# Schematic.net
KiCad netlist of a schematic drawn in EAGLE
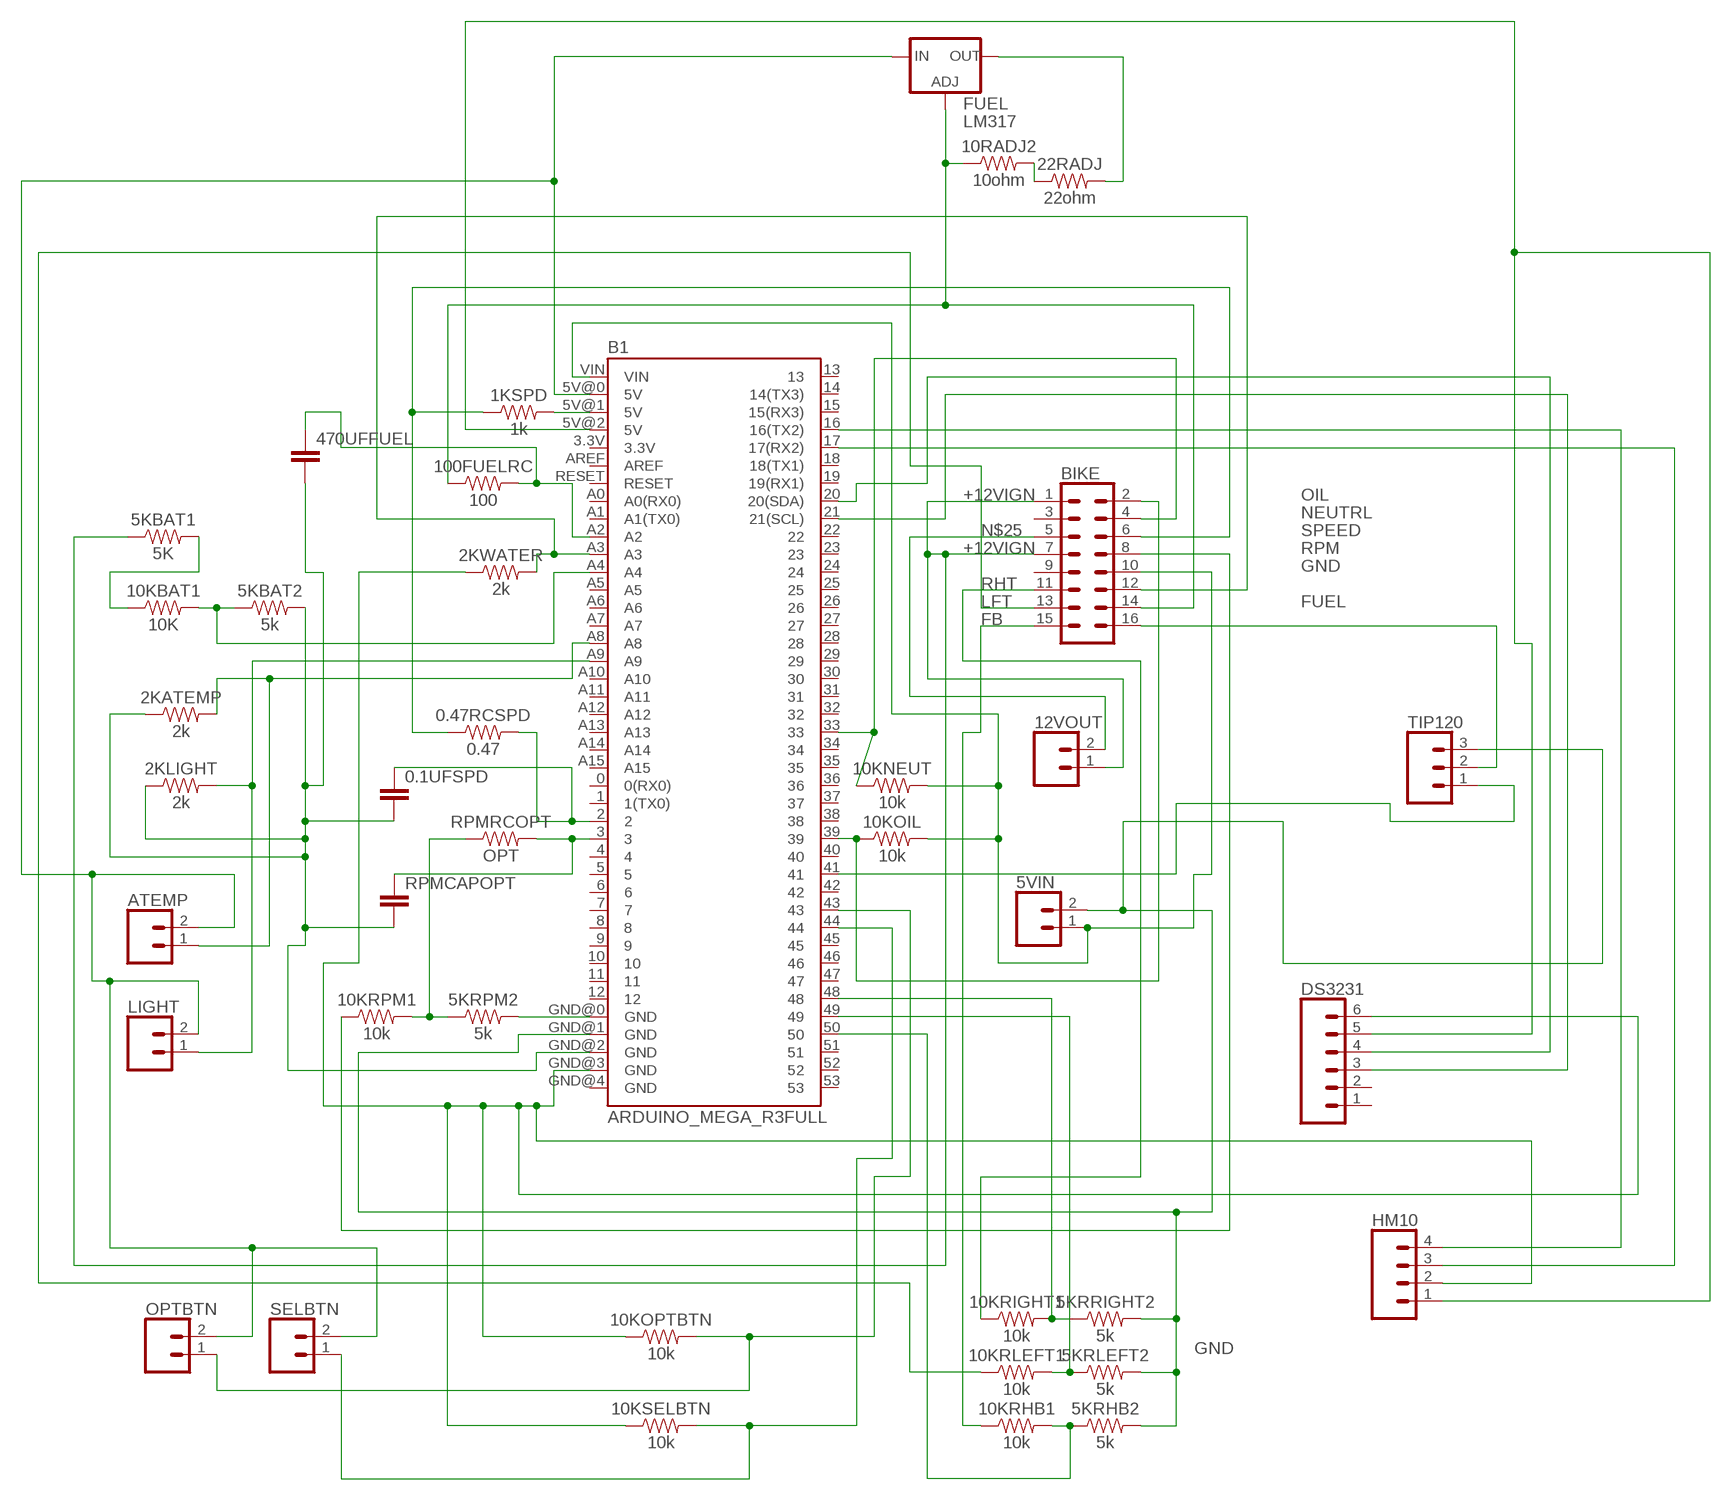
[diagram p0: schematic, sheet 1]

(export (version "E")
  (design (tool "Eeschema 10.0.6"))
  (components
    (comp (ref "0.1UFSPD")
      (value "C2,5-3")
      (footprint "eagle-import:C2.5-3")
      (libsource (lib "eagle-import") (part "C2,5-3"))
    )
    (comp (ref "0.47RCSPD")
      (value "0.47")
      (footprint "eagle-import:AXIAL-0.3")
      (libsource (lib "eagle-import") (part "1KOHM-HORIZ-1/4W-5%"))
    )
    (comp (ref "1KSPD")
      (value "1k")
      (footprint "eagle-import:AXIAL-0.3")
      (libsource (lib "eagle-import") (part "1KOHM-HORIZ-1/4W-5%"))
    )
    (comp (ref "2KATEMP")
      (value "2k")
      (footprint "eagle-import:AXIAL-0.3")
      (libsource (lib "eagle-import") (part "1KOHM-HORIZ-1/4W-5%"))
    )
    (comp (ref "2KLIGHT")
      (value "2k")
      (footprint "eagle-import:AXIAL-0.3")
      (libsource (lib "eagle-import") (part "1KOHM-HORIZ-1/4W-5%"))
    )
    (comp (ref "2KWATER")
      (value "2k")
      (footprint "eagle-import:AXIAL-0.3")
      (libsource (lib "eagle-import") (part "1KOHM-HORIZ-1/4W-5%"))
    )
    (comp (ref "5KBAT1")
      (value "5K")
      (footprint "eagle-import:AXIAL-0.3")
      (libsource (lib "eagle-import") (part "1KOHM-HORIZ-1/4W-5%"))
    )
    (comp (ref "5KBAT2")
      (value "5k")
      (footprint "eagle-import:AXIAL-0.3")
      (libsource (lib "eagle-import") (part "1KOHM-HORIZ-1/4W-5%"))
    )
    (comp (ref "5KRHB2")
      (value "5k")
      (footprint "eagle-import:AXIAL-0.3")
      (libsource (lib "eagle-import") (part "1KOHM-HORIZ-1/4W-5%"))
    )
    (comp (ref "5KRLEFT2")
      (value "5k")
      (footprint "eagle-import:AXIAL-0.3")
      (libsource (lib "eagle-import") (part "1KOHM-HORIZ-1/4W-5%"))
    )
    (comp (ref "5KRPM2")
      (value "5k")
      (footprint "eagle-import:AXIAL-0.3")
      (libsource (lib "eagle-import") (part "1KOHM-HORIZ-1/4W-5%"))
    )
    (comp (ref "5KRRIGHT2")
      (value "5k")
      (footprint "eagle-import:AXIAL-0.3")
      (libsource (lib "eagle-import") (part "1KOHM-HORIZ-1/4W-5%"))
    )
    (comp (ref "5VIN")
      (value "CONN_02PTH4")
      (footprint "eagle-import:1X02_XTRA_BIG")
      (libsource (lib "eagle-import") (part "CONN_02PTH4"))
    )
    (comp (ref "10KBAT1")
      (value "10K")
      (footprint "eagle-import:AXIAL-0.3")
      (libsource (lib "eagle-import") (part "1KOHM-HORIZ-1/4W-5%"))
    )
    (comp (ref "10KNEUT")
      (value "10k")
      (footprint "eagle-import:AXIAL-0.3")
      (libsource (lib "eagle-import") (part "1KOHM-HORIZ-1/4W-5%"))
    )
    (comp (ref "10KOIL")
      (value "10k")
      (footprint "eagle-import:AXIAL-0.3")
      (libsource (lib "eagle-import") (part "1KOHM-HORIZ-1/4W-5%"))
    )
    (comp (ref "10KOPTBTN")
      (value "10k")
      (footprint "eagle-import:AXIAL-0.3")
      (libsource (lib "eagle-import") (part "1KOHM-HORIZ-1/4W-5%"))
    )
    (comp (ref "10KRHB1")
      (value "10k")
      (footprint "eagle-import:AXIAL-0.3")
      (libsource (lib "eagle-import") (part "1KOHM-HORIZ-1/4W-5%"))
    )
    (comp (ref "10KRIGHT1")
      (value "10k")
      (footprint "eagle-import:AXIAL-0.3")
      (libsource (lib "eagle-import") (part "1KOHM-HORIZ-1/4W-5%"))
    )
    (comp (ref "10KRLEFT1")
      (value "10k")
      (footprint "eagle-import:AXIAL-0.3")
      (libsource (lib "eagle-import") (part "1KOHM-HORIZ-1/4W-5%"))
    )
    (comp (ref "10KRPM1")
      (value "10k")
      (footprint "eagle-import:AXIAL-0.3")
      (libsource (lib "eagle-import") (part "1KOHM-HORIZ-1/4W-5%"))
    )
    (comp (ref "10KSELBTN")
      (value "10k")
      (footprint "eagle-import:AXIAL-0.3")
      (libsource (lib "eagle-import") (part "1KOHM-HORIZ-1/4W-5%"))
    )
    (comp (ref "10RADJ2")
      (value "10ohm")
      (footprint "eagle-import:AXIAL-0.3")
      (libsource (lib "eagle-import") (part "1KOHM-HORIZ-1/4W-5%"))
    )
    (comp (ref "12VOUT")
      (value "CONN_02PTH4")
      (footprint "eagle-import:1X02_XTRA_BIG")
      (libsource (lib "eagle-import") (part "CONN_02PTH4"))
    )
    (comp (ref "22RADJ")
      (value "22ohm")
      (footprint "eagle-import:AXIAL-0.3")
      (libsource (lib "eagle-import") (part "1KOHM-HORIZ-1/4W-5%"))
    )
    (comp (ref "100FUELRC")
      (value "100")
      (footprint "eagle-import:AXIAL-0.3")
      (libsource (lib "eagle-import") (part "1KOHM-HORIZ-1/4W-5%"))
    )
    (comp (ref "470UFFUEL")
      (value "C2,5-3")
      (footprint "eagle-import:C2.5-3")
      (libsource (lib "eagle-import") (part "C2,5-3"))
    )
    (comp (ref "ATEMP")
      (value "CONN_02")
      (footprint "eagle-import:1X02")
      (libsource (lib "eagle-import") (part "CONN_02"))
    )
    (comp (ref "B1")
      (value "ARDUINO_MEGA_R3FULL")
      (footprint "eagle-import:ARDUINO_MEGA")
      (libsource (lib "eagle-import") (part "ARDUINO_MEGA_R3FULL"))
    )
    (comp (ref "BIKE")
      (value "CONN_08X2")
      (footprint "eagle-import:2X8")
      (libsource (lib "eagle-import") (part "CONN_08X2"))
    )
    (comp (ref "DS3231")
      (value "CONN_06SILK_FEMALE_PTH")
      (footprint "eagle-import:1X06")
      (libsource (lib "eagle-import") (part "CONN_06SILK_FEMALE_PTH"))
    )
    (comp (ref "FUEL")
      (value "LM317")
      (footprint "eagle-import:TO220-ADJ")
      (libsource (lib "eagle-import") (part "V_REG_317SINK"))
    )
    (comp (ref "HM10")
      (value "CONN_04")
      (footprint "eagle-import:1X04")
      (libsource (lib "eagle-import") (part "CONN_04"))
    )
    (comp (ref "LIGHT")
      (value "CONN_02")
      (footprint "eagle-import:1X02")
      (libsource (lib "eagle-import") (part "CONN_02"))
    )
    (comp (ref "OPTBTN")
      (value "CONN_02")
      (footprint "eagle-import:1X02")
      (libsource (lib "eagle-import") (part "CONN_02"))
    )
    (comp (ref "RPMCAPOPT")
      (value "C2,5-3")
      (footprint "eagle-import:C2.5-3")
      (libsource (lib "eagle-import") (part "C2,5-3"))
    )
    (comp (ref "RPMRCOPT")
      (value "OPT")
      (footprint "eagle-import:AXIAL-0.3")
      (libsource (lib "eagle-import") (part "1KOHM-HORIZ-1/4W-5%"))
    )
    (comp (ref "SELBTN")
      (value "CONN_02")
      (footprint "eagle-import:1X02")
      (libsource (lib "eagle-import") (part "CONN_02"))
    )
    (comp (ref "TIP120")
      (value "CONN_03")
      (footprint "eagle-import:1X03")
      (libsource (lib "eagle-import") (part "CONN_03"))
    )
  )
  (nets
    (net (code "1") (name "/+12VIGN") (class "Default")
      (node (ref "12VOUT") (pin "1") (pinfunction "1_1") (pintype "passive"))
      (node (ref "5KBAT1") (pin "P$1") (pinfunction "1_P$1") (pintype "passive"))
      (node (ref "BIKE") (pin "1") (pinfunction "1_1") (pintype "passive"))
      (node (ref "BIKE") (pin "7") (pinfunction "7_7") (pintype "passive"))
    )
    (net (code "2") (name "/FB") (class "Default")
      (node (ref "10KRHB1") (pin "P$1") (pinfunction "1_P$1") (pintype "passive"))
      (node (ref "BIKE") (pin "15") (pinfunction "15_15") (pintype "passive"))
    )
    (net (code "3") (name "/FUEL") (class "Default")
      (node (ref "100FUELRC") (pin "P$1") (pinfunction "1_P$1") (pintype "passive"))
      (node (ref "10RADJ2") (pin "P$1") (pinfunction "1_P$1") (pintype "passive"))
      (node (ref "BIKE") (pin "14") (pinfunction "14_14") (pintype "passive"))
      (node (ref "FUEL") (pin "ADJ") (pinfunction "ADJ_ADJ") (pintype "input"))
    )
    (net (code "4") (name "/GND") (class "Default")
      (node (ref "5KRHB2") (pin "P$2") (pinfunction "2_P$2") (pintype "passive"))
      (node (ref "5KRLEFT2") (pin "P$2") (pinfunction "2_P$2") (pintype "passive"))
      (node (ref "5KRRIGHT2") (pin "P$2") (pinfunction "2_P$2") (pintype "passive"))
      (node (ref "5VIN") (pin "2") (pinfunction "2_2") (pintype "passive"))
      (node (ref "B1") (pin "GND@1") (pinfunction "GND_GND@1") (pintype "bidirectional"))
      (node (ref "TIP120") (pin "3") (pinfunction "3_3") (pintype "passive"))
    )
    (net (code "5") (name "/LFT") (class "Default")
      (node (ref "10KRLEFT1") (pin "P$1") (pinfunction "1_P$1") (pintype "passive"))
      (node (ref "BIKE") (pin "13") (pinfunction "13_13") (pintype "passive"))
    )
    (net (code "6") (name "/N$25") (class "Default")
      (node (ref "12VOUT") (pin "2") (pinfunction "2_2") (pintype "passive"))
      (node (ref "BIKE") (pin "5") (pinfunction "5_5") (pintype "passive"))
    )
    (net (code "7") (name "/NEUTRL") (class "Default")
      (node (ref "10KNEUT") (pin "P$1") (pinfunction "1_P$1") (pintype "passive"))
      (node (ref "B1") (pin "33") (pinfunction "33_33") (pintype "bidirectional"))
      (node (ref "BIKE") (pin "4") (pinfunction "4_4") (pintype "passive"))
    )
    (net (code "8") (name "/OIL") (class "Default")
      (node (ref "10KOIL") (pin "P$1") (pinfunction "1_P$1") (pintype "passive"))
      (node (ref "B1") (pin "39") (pinfunction "39_39") (pintype "bidirectional"))
      (node (ref "BIKE") (pin "2") (pinfunction "2_2") (pintype "passive"))
    )
    (net (code "9") (name "/RHT") (class "Default")
      (node (ref "10KRIGHT1") (pin "P$1") (pinfunction "1_P$1") (pintype "passive"))
      (node (ref "BIKE") (pin "11") (pinfunction "11_11") (pintype "passive"))
    )
    (net (code "10") (name "/RPM") (class "Default")
      (node (ref "10KRPM1") (pin "P$1") (pinfunction "1_P$1") (pintype "passive"))
      (node (ref "BIKE") (pin "8") (pinfunction "8_8") (pintype "passive"))
    )
    (net (code "11") (name "/SPEED") (class "Default")
      (node (ref "0.47RCSPD") (pin "P$1") (pinfunction "1_P$1") (pintype "passive"))
      (node (ref "1KSPD") (pin "P$1") (pinfunction "1_P$1") (pintype "passive"))
      (node (ref "BIKE") (pin "6") (pinfunction "6_6") (pintype "passive"))
    )
    (net (code "12") (name "Net-(0.47RCSPD-2)") (class "Default")
      (node (ref "0.1UFSPD") (pin "1") (pinfunction "1_1") (pintype "passive"))
      (node (ref "0.47RCSPD") (pin "P$2") (pinfunction "2_P$2") (pintype "passive"))
      (node (ref "B1") (pin "2") (pinfunction "2_2") (pintype "bidirectional"))
    )
    (net (code "13") (name "Net-(1KSPD-2)") (class "Default")
      (node (ref "1KSPD") (pin "P$2") (pinfunction "2_P$2") (pintype "passive"))
      (node (ref "B1") (pin "5V@1") (pinfunction "5V_5V@1") (pintype "bidirectional"))
    )
    (net (code "14") (name "Net-(2KATEMP-1)") (class "Default")
      (node (ref "0.1UFSPD") (pin "2") (pinfunction "2_2") (pintype "passive"))
      (node (ref "2KATEMP") (pin "P$1") (pinfunction "1_P$1") (pintype "passive"))
      (node (ref "2KLIGHT") (pin "P$1") (pinfunction "1_P$1") (pintype "passive"))
      (node (ref "470UFFUEL") (pin "2") (pinfunction "2_2") (pintype "passive"))
      (node (ref "5KBAT2") (pin "P$2") (pinfunction "2_P$2") (pintype "passive"))
      (node (ref "B1") (pin "GND@2") (pinfunction "GND_GND@2") (pintype "bidirectional"))
      (node (ref "RPMCAPOPT") (pin "2") (pinfunction "2_2") (pintype "passive"))
    )
    (net (code "15") (name "Net-(2KATEMP-2)") (class "Default")
      (node (ref "2KATEMP") (pin "P$2") (pinfunction "2_P$2") (pintype "passive"))
      (node (ref "ATEMP") (pin "1") (pinfunction "1_1") (pintype "passive"))
      (node (ref "B1") (pin "A8") (pinfunction "A8_A8") (pintype "bidirectional"))
    )
    (net (code "16") (name "Net-(2KLIGHT-2)") (class "Default")
      (node (ref "2KLIGHT") (pin "P$2") (pinfunction "2_P$2") (pintype "passive"))
      (node (ref "B1") (pin "A9") (pinfunction "A9_A9") (pintype "bidirectional"))
      (node (ref "LIGHT") (pin "1") (pinfunction "1_1") (pintype "passive"))
    )
    (net (code "17") (name "Net-(2KWATER-2)") (class "Default")
      (node (ref "2KWATER") (pin "P$2") (pinfunction "2_P$2") (pintype "passive"))
      (node (ref "B1") (pin "A3") (pinfunction "A3_A3") (pintype "bidirectional"))
      (node (ref "BIKE") (pin "12") (pinfunction "12_12") (pintype "passive"))
    )
    (net (code "18") (name "Net-(5KRPM2-2)") (class "Default")
      (node (ref "5KRPM2") (pin "P$2") (pinfunction "2_P$2") (pintype "passive"))
      (node (ref "B1") (pin "GND@0") (pinfunction "GND_GND@0") (pintype "bidirectional"))
    )
    (net (code "19") (name "Net-(10KBAT1-1)") (class "Default")
      (node (ref "10KBAT1") (pin "P$1") (pinfunction "1_P$1") (pintype "passive"))
      (node (ref "5KBAT1") (pin "P$2") (pinfunction "2_P$2") (pintype "passive"))
    )
    (net (code "20") (name "Net-(10KBAT1-2)") (class "Default")
      (node (ref "10KBAT1") (pin "P$2") (pinfunction "2_P$2") (pintype "passive"))
      (node (ref "5KBAT2") (pin "P$1") (pinfunction "1_P$1") (pintype "passive"))
      (node (ref "B1") (pin "A4") (pinfunction "A4_A4") (pintype "bidirectional"))
    )
    (net (code "21") (name "Net-(10KNEUT-2)") (class "Default")
      (node (ref "10KNEUT") (pin "P$2") (pinfunction "2_P$2") (pintype "passive"))
      (node (ref "10KOIL") (pin "P$2") (pinfunction "2_P$2") (pintype "passive"))
      (node (ref "5VIN") (pin "1") (pinfunction "1_1") (pintype "passive"))
      (node (ref "B1") (pin "VIN") (pinfunction "VIN_VIN") (pintype "bidirectional"))
      (node (ref "BIKE") (pin "10") (pinfunction "10_10") (pintype "passive"))
    )
    (net (code "22") (name "Net-(10KOPTBTN-1)") (class "Default")
      (node (ref "10KOPTBTN") (pin "P$1") (pinfunction "1_P$1") (pintype "passive"))
      (node (ref "10KSELBTN") (pin "P$1") (pinfunction "1_P$1") (pintype "passive"))
      (node (ref "2KWATER") (pin "P$1") (pinfunction "1_P$1") (pintype "passive"))
      (node (ref "B1") (pin "GND@3") (pinfunction "GND_GND@3") (pintype "bidirectional"))
      (node (ref "DS3231") (pin "6") (pinfunction "6_6") (pintype "passive"))
      (node (ref "HM10") (pin "2") (pinfunction "2_2") (pintype "passive"))
    )
    (net (code "23") (name "Net-(10KOPTBTN-2)") (class "Default")
      (node (ref "10KOPTBTN") (pin "P$2") (pinfunction "2_P$2") (pintype "passive"))
      (node (ref "B1") (pin "43") (pinfunction "43_43") (pintype "bidirectional"))
      (node (ref "OPTBTN") (pin "1") (pinfunction "1_1") (pintype "passive"))
    )
    (net (code "24") (name "Net-(10KRHB1-2)") (class "Default")
      (node (ref "10KRHB1") (pin "P$2") (pinfunction "2_P$2") (pintype "passive"))
      (node (ref "5KRHB2") (pin "P$1") (pinfunction "1_P$1") (pintype "passive"))
      (node (ref "B1") (pin "50") (pinfunction "50_50") (pintype "bidirectional"))
    )
    (net (code "25") (name "Net-(10KRIGHT1-2)") (class "Default")
      (node (ref "10KRIGHT1") (pin "P$2") (pinfunction "2_P$2") (pintype "passive"))
      (node (ref "5KRRIGHT2") (pin "P$1") (pinfunction "1_P$1") (pintype "passive"))
      (node (ref "B1") (pin "48") (pinfunction "48_48") (pintype "bidirectional"))
    )
    (net (code "26") (name "Net-(10KRLEFT1-2)") (class "Default")
      (node (ref "10KRLEFT1") (pin "P$2") (pinfunction "2_P$2") (pintype "passive"))
      (node (ref "5KRLEFT2") (pin "P$1") (pinfunction "1_P$1") (pintype "passive"))
      (node (ref "B1") (pin "49") (pinfunction "49_49") (pintype "bidirectional"))
    )
    (net (code "27") (name "Net-(10KRPM1-2)") (class "Default")
      (node (ref "10KRPM1") (pin "P$2") (pinfunction "2_P$2") (pintype "passive"))
      (node (ref "5KRPM2") (pin "P$1") (pinfunction "1_P$1") (pintype "passive"))
      (node (ref "RPMRCOPT") (pin "P$1") (pinfunction "1_P$1") (pintype "passive"))
    )
    (net (code "28") (name "Net-(10KSELBTN-2)") (class "Default")
      (node (ref "10KSELBTN") (pin "P$2") (pinfunction "2_P$2") (pintype "passive"))
      (node (ref "B1") (pin "44") (pinfunction "44_44") (pintype "bidirectional"))
      (node (ref "SELBTN") (pin "1") (pinfunction "1_1") (pintype "passive"))
    )
    (net (code "29") (name "Net-(10RADJ2-2)") (class "Default")
      (node (ref "10RADJ2") (pin "P$2") (pinfunction "2_P$2") (pintype "passive"))
      (node (ref "22RADJ") (pin "P$1") (pinfunction "1_P$1") (pintype "passive"))
    )
    (net (code "30") (name "Net-(22RADJ-2)") (class "Default")
      (node (ref "22RADJ") (pin "P$2") (pinfunction "2_P$2") (pintype "passive"))
      (node (ref "FUEL") (pin "OUT") (pinfunction "OUT_OUT") (pintype "output"))
    )
    (net (code "31") (name "Net-(100FUELRC-2)") (class "Default")
      (node (ref "100FUELRC") (pin "P$2") (pinfunction "2_P$2") (pintype "passive"))
      (node (ref "470UFFUEL") (pin "1") (pinfunction "1_1") (pintype "passive"))
      (node (ref "B1") (pin "A2") (pinfunction "A2_A2") (pintype "bidirectional"))
    )
    (net (code "32") (name "Net-(ATEMP-Pad2)") (class "Default")
      (node (ref "ATEMP") (pin "2") (pinfunction "2_2") (pintype "passive"))
      (node (ref "B1") (pin "5V@0") (pinfunction "5V_5V@0") (pintype "bidirectional"))
      (node (ref "FUEL") (pin "IN") (pinfunction "IN_IN") (pintype "input"))
      (node (ref "LIGHT") (pin "2") (pinfunction "2_2") (pintype "passive"))
      (node (ref "OPTBTN") (pin "2") (pinfunction "2_2") (pintype "passive"))
      (node (ref "SELBTN") (pin "2") (pinfunction "2_2") (pintype "passive"))
    )
    (net (code "33") (name "Net-(B1-5V-Pad5V@2)") (class "Default")
      (node (ref "B1") (pin "5V@2") (pinfunction "5V_5V@2") (pintype "bidirectional"))
      (node (ref "DS3231") (pin "5") (pinfunction "5_5") (pintype "passive"))
      (node (ref "HM10") (pin "1") (pinfunction "1_1") (pintype "passive"))
    )
    (net (code "34") (name "Net-(B1-16(TX2))") (class "Default")
      (node (ref "B1") (pin "16") (pinfunction "16(TX2)_16") (pintype "bidirectional"))
      (node (ref "HM10") (pin "4") (pinfunction "4_4") (pintype "passive"))
    )
    (net (code "35") (name "Net-(B1-17(RX2))") (class "Default")
      (node (ref "B1") (pin "17") (pinfunction "17(RX2)_17") (pintype "bidirectional"))
      (node (ref "HM10") (pin "3") (pinfunction "3_3") (pintype "passive"))
    )
    (net (code "36") (name "Net-(B1-20(SDA))") (class "Default")
      (node (ref "B1") (pin "20") (pinfunction "20(SDA)_20") (pintype "bidirectional"))
      (node (ref "DS3231") (pin "4") (pinfunction "4_4") (pintype "passive"))
    )
    (net (code "37") (name "Net-(B1-21(SCL))") (class "Default")
      (node (ref "B1") (pin "21") (pinfunction "21(SCL)_21") (pintype "bidirectional"))
      (node (ref "DS3231") (pin "3") (pinfunction "3_3") (pintype "passive"))
    )
    (net (code "38") (name "Net-(B1-Pad41)") (class "Default")
      (node (ref "B1") (pin "41") (pinfunction "41_41") (pintype "bidirectional"))
      (node (ref "TIP120") (pin "1") (pinfunction "1_1") (pintype "passive"))
    )
    (net (code "39") (name "Net-(BIKE-Pad16)") (class "Default")
      (node (ref "BIKE") (pin "16") (pinfunction "16_16") (pintype "passive"))
      (node (ref "TIP120") (pin "2") (pinfunction "2_2") (pintype "passive"))
    )
    (net (code "40") (name "Net-(RPMRCOPT-2)") (class "Default")
      (node (ref "B1") (pin "3") (pinfunction "3_3") (pintype "bidirectional"))
      (node (ref "RPMCAPOPT") (pin "1") (pinfunction "1_1") (pintype "passive"))
      (node (ref "RPMRCOPT") (pin "P$2") (pinfunction "2_P$2") (pintype "passive"))
    )
    (net (code "41") (name "unconnected-(B1-0(RX0)-Pad0)") (class "Default")
      (node (ref "B1") (pin "0") (pinfunction "0(RX0)_0") (pintype "bidirectional"))
    )
    (net (code "42") (name "unconnected-(B1-1(TX0)-Pad1)") (class "Default")
      (node (ref "B1") (pin "1") (pinfunction "1(TX0)_1") (pintype "bidirectional"))
    )
    (net (code "43") (name "unconnected-(B1-14(TX3)-Pad14)") (class "Default")
      (node (ref "B1") (pin "14") (pinfunction "14(TX3)_14") (pintype "bidirectional"))
    )
    (net (code "44") (name "unconnected-(B1-15(RX3)-Pad15)") (class "Default")
      (node (ref "B1") (pin "15") (pinfunction "15(RX3)_15") (pintype "bidirectional"))
    )
    (net (code "45") (name "unconnected-(B1-18(TX1)-Pad18)") (class "Default")
      (node (ref "B1") (pin "18") (pinfunction "18(TX1)_18") (pintype "bidirectional"))
    )
    (net (code "46") (name "unconnected-(B1-19(RX1)-Pad19)") (class "Default")
      (node (ref "B1") (pin "19") (pinfunction "19(RX1)_19") (pintype "bidirectional"))
    )
    (net (code "47") (name "unconnected-(B1-A0(RX0)-PadA0)") (class "Default")
      (node (ref "B1") (pin "A0") (pinfunction "A0(RX0)_A0") (pintype "bidirectional"))
    )
    (net (code "48") (name "unconnected-(B1-A1(TX0)-PadA1)") (class "Default")
      (node (ref "B1") (pin "A1") (pinfunction "A1(TX0)_A1") (pintype "bidirectional"))
    )
    (net (code "49") (name "unconnected-(B1-GND-PadGND@4)") (class "Default")
      (node (ref "B1") (pin "GND@4") (pinfunction "GND_GND@4") (pintype "bidirectional"))
    )
    (net (code "50") (name "unconnected-(B1-Pad3.3V)") (class "Default")
      (node (ref "B1") (pin "3.3V") (pinfunction "3.3V_3.3V") (pintype "bidirectional"))
    )
    (net (code "51") (name "unconnected-(B1-Pad4)") (class "Default")
      (node (ref "B1") (pin "4") (pinfunction "4_4") (pintype "bidirectional"))
    )
    (net (code "52") (name "unconnected-(B1-Pad5)") (class "Default")
      (node (ref "B1") (pin "5") (pinfunction "5_5") (pintype "bidirectional"))
    )
    (net (code "53") (name "unconnected-(B1-Pad6)") (class "Default")
      (node (ref "B1") (pin "6") (pinfunction "6_6") (pintype "bidirectional"))
    )
    (net (code "54") (name "unconnected-(B1-Pad7)") (class "Default")
      (node (ref "B1") (pin "7") (pinfunction "7_7") (pintype "bidirectional"))
    )
    (net (code "55") (name "unconnected-(B1-Pad8)") (class "Default")
      (node (ref "B1") (pin "8") (pinfunction "8_8") (pintype "bidirectional"))
    )
    (net (code "56") (name "unconnected-(B1-Pad9)") (class "Default")
      (node (ref "B1") (pin "9") (pinfunction "9_9") (pintype "bidirectional"))
    )
    (net (code "57") (name "unconnected-(B1-Pad10)") (class "Default")
      (node (ref "B1") (pin "10") (pinfunction "10_10") (pintype "bidirectional"))
    )
    (net (code "58") (name "unconnected-(B1-Pad11)") (class "Default")
      (node (ref "B1") (pin "11") (pinfunction "11_11") (pintype "bidirectional"))
    )
    (net (code "59") (name "unconnected-(B1-Pad12)") (class "Default")
      (node (ref "B1") (pin "12") (pinfunction "12_12") (pintype "bidirectional"))
    )
    (net (code "60") (name "unconnected-(B1-Pad13)") (class "Default")
      (node (ref "B1") (pin "13") (pinfunction "13_13") (pintype "bidirectional"))
    )
    (net (code "61") (name "unconnected-(B1-Pad22)") (class "Default")
      (node (ref "B1") (pin "22") (pinfunction "22_22") (pintype "bidirectional"))
    )
    (net (code "62") (name "unconnected-(B1-Pad23)") (class "Default")
      (node (ref "B1") (pin "23") (pinfunction "23_23") (pintype "bidirectional"))
    )
    (net (code "63") (name "unconnected-(B1-Pad24)") (class "Default")
      (node (ref "B1") (pin "24") (pinfunction "24_24") (pintype "bidirectional"))
    )
    (net (code "64") (name "unconnected-(B1-Pad25)") (class "Default")
      (node (ref "B1") (pin "25") (pinfunction "25_25") (pintype "bidirectional"))
    )
    (net (code "65") (name "unconnected-(B1-Pad26)") (class "Default")
      (node (ref "B1") (pin "26") (pinfunction "26_26") (pintype "bidirectional"))
    )
    (net (code "66") (name "unconnected-(B1-Pad27)") (class "Default")
      (node (ref "B1") (pin "27") (pinfunction "27_27") (pintype "bidirectional"))
    )
    (net (code "67") (name "unconnected-(B1-Pad28)") (class "Default")
      (node (ref "B1") (pin "28") (pinfunction "28_28") (pintype "bidirectional"))
    )
    (net (code "68") (name "unconnected-(B1-Pad29)") (class "Default")
      (node (ref "B1") (pin "29") (pinfunction "29_29") (pintype "bidirectional"))
    )
    (net (code "69") (name "unconnected-(B1-Pad30)") (class "Default")
      (node (ref "B1") (pin "30") (pinfunction "30_30") (pintype "bidirectional"))
    )
    (net (code "70") (name "unconnected-(B1-Pad31)") (class "Default")
      (node (ref "B1") (pin "31") (pinfunction "31_31") (pintype "bidirectional"))
    )
    (net (code "71") (name "unconnected-(B1-Pad32)") (class "Default")
      (node (ref "B1") (pin "32") (pinfunction "32_32") (pintype "bidirectional"))
    )
    (net (code "72") (name "unconnected-(B1-Pad34)") (class "Default")
      (node (ref "B1") (pin "34") (pinfunction "34_34") (pintype "bidirectional"))
    )
    (net (code "73") (name "unconnected-(B1-Pad35)") (class "Default")
      (node (ref "B1") (pin "35") (pinfunction "35_35") (pintype "bidirectional"))
    )
    (net (code "74") (name "unconnected-(B1-Pad36)") (class "Default")
      (node (ref "B1") (pin "36") (pinfunction "36_36") (pintype "bidirectional"))
    )
    (net (code "75") (name "unconnected-(B1-Pad37)") (class "Default")
      (node (ref "B1") (pin "37") (pinfunction "37_37") (pintype "bidirectional"))
    )
    (net (code "76") (name "unconnected-(B1-Pad38)") (class "Default")
      (node (ref "B1") (pin "38") (pinfunction "38_38") (pintype "bidirectional"))
    )
    (net (code "77") (name "unconnected-(B1-Pad40)") (class "Default")
      (node (ref "B1") (pin "40") (pinfunction "40_40") (pintype "bidirectional"))
    )
    (net (code "78") (name "unconnected-(B1-Pad42)") (class "Default")
      (node (ref "B1") (pin "42") (pinfunction "42_42") (pintype "bidirectional"))
    )
    (net (code "79") (name "unconnected-(B1-Pad45)") (class "Default")
      (node (ref "B1") (pin "45") (pinfunction "45_45") (pintype "bidirectional"))
    )
    (net (code "80") (name "unconnected-(B1-Pad46)") (class "Default")
      (node (ref "B1") (pin "46") (pinfunction "46_46") (pintype "bidirectional"))
    )
    (net (code "81") (name "unconnected-(B1-Pad47)") (class "Default")
      (node (ref "B1") (pin "47") (pinfunction "47_47") (pintype "bidirectional"))
    )
    (net (code "82") (name "unconnected-(B1-Pad51)") (class "Default")
      (node (ref "B1") (pin "51") (pinfunction "51_51") (pintype "bidirectional"))
    )
    (net (code "83") (name "unconnected-(B1-Pad52)") (class "Default")
      (node (ref "B1") (pin "52") (pinfunction "52_52") (pintype "bidirectional"))
    )
    (net (code "84") (name "unconnected-(B1-Pad53)") (class "Default")
      (node (ref "B1") (pin "53") (pinfunction "53_53") (pintype "bidirectional"))
    )
    (net (code "85") (name "unconnected-(B1-PadA5)") (class "Default")
      (node (ref "B1") (pin "A5") (pinfunction "A5_A5") (pintype "bidirectional"))
    )
    (net (code "86") (name "unconnected-(B1-PadA6)") (class "Default")
      (node (ref "B1") (pin "A6") (pinfunction "A6_A6") (pintype "bidirectional"))
    )
    (net (code "87") (name "unconnected-(B1-PadA7)") (class "Default")
      (node (ref "B1") (pin "A7") (pinfunction "A7_A7") (pintype "bidirectional"))
    )
    (net (code "88") (name "unconnected-(B1-PadA10)") (class "Default")
      (node (ref "B1") (pin "A10") (pinfunction "A10_A10") (pintype "bidirectional"))
    )
    (net (code "89") (name "unconnected-(B1-PadA11)") (class "Default")
      (node (ref "B1") (pin "A11") (pinfunction "A11_A11") (pintype "bidirectional"))
    )
    (net (code "90") (name "unconnected-(B1-PadA12)") (class "Default")
      (node (ref "B1") (pin "A12") (pinfunction "A12_A12") (pintype "bidirectional"))
    )
    (net (code "91") (name "unconnected-(B1-PadA13)") (class "Default")
      (node (ref "B1") (pin "A13") (pinfunction "A13_A13") (pintype "bidirectional"))
    )
    (net (code "92") (name "unconnected-(B1-PadA14)") (class "Default")
      (node (ref "B1") (pin "A14") (pinfunction "A14_A14") (pintype "bidirectional"))
    )
    (net (code "93") (name "unconnected-(B1-PadA15)") (class "Default")
      (node (ref "B1") (pin "A15") (pinfunction "A15_A15") (pintype "bidirectional"))
    )
    (net (code "94") (name "unconnected-(B1-PadAREF)") (class "Default")
      (node (ref "B1") (pin "AREF") (pinfunction "AREF_AREF") (pintype "bidirectional"))
    )
    (net (code "95") (name "unconnected-(B1-PadRESET)") (class "Default")
      (node (ref "B1") (pin "RESET") (pinfunction "RESET_RESET") (pintype "bidirectional"))
    )
    (net (code "96") (name "unconnected-(BIKE-Pad3)") (class "Default")
      (node (ref "BIKE") (pin "3") (pinfunction "3_3") (pintype "passive"))
    )
    (net (code "97") (name "unconnected-(BIKE-Pad9)") (class "Default")
      (node (ref "BIKE") (pin "9") (pinfunction "9_9") (pintype "passive"))
    )
    (net (code "98") (name "unconnected-(DS3231-Pad1)") (class "Default")
      (node (ref "DS3231") (pin "1") (pinfunction "1_1") (pintype "passive"))
    )
    (net (code "99") (name "unconnected-(DS3231-Pad2)") (class "Default")
      (node (ref "DS3231") (pin "2") (pinfunction "2_2") (pintype "passive"))
    )
  )
)
